# MP_RS485.net
KiCad netlist of a schematic drawn in Altium Designer
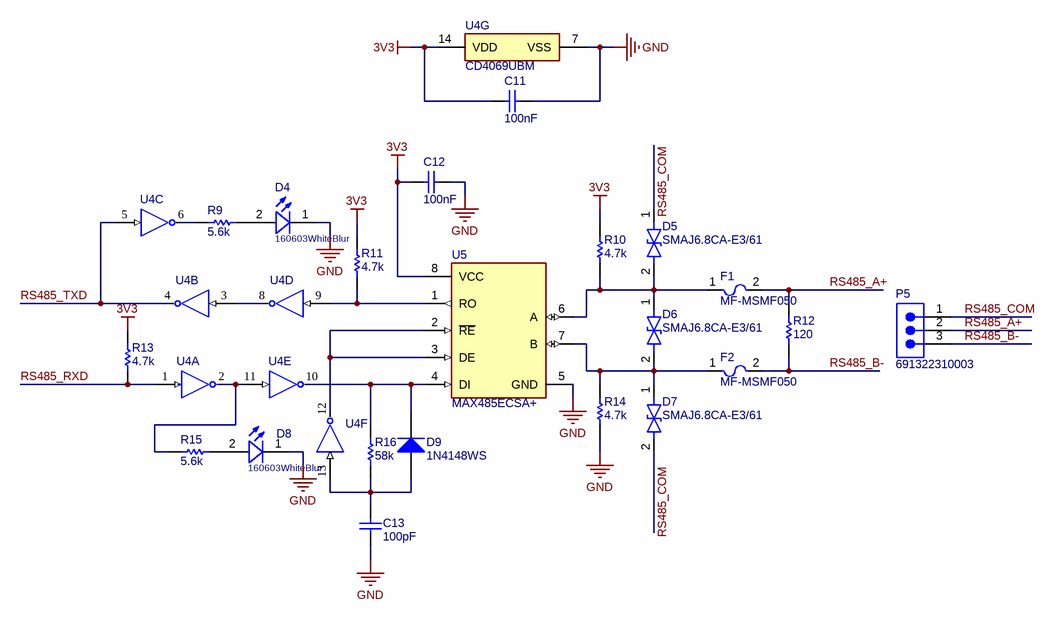
[diagram p0: [MP] RS485.SchDoc]

(export (version "E")
  (design (tool "Eeschema 10.0.6"))
  (components
    (comp (ref "C11")
      (value "100nF")
      (footprint "CAP_0603")
      (description "CAP, size 0603, 100 nF, 50 VDC, 10%")
      (fields
        (field (name "MANUFACTURER PART NUMBER") "CGA3E3X8R1H104K080AE")
        (field (name "LCSC PART #") "C14663")
        (field (name "SOURCE") "Capacitor_0603_10_percent.SchLib")
      )
      (libsource (lib "University of Technology") (part "010603475106.3"))
    )
    (comp (ref "C12")
      (value "100nF")
      (footprint "CAP_0603")
      (description "CAP, size 0603, 100 nF, 50 VDC, 10%")
      (fields
        (field (name "MANUFACTURER PART NUMBER") "CGA3E3X8R1H104K080AE")
        (field (name "LCSC PART #") "C14663")
        (field (name "SOURCE") "Capacitor_0603_10_percent.SchLib")
      )
      (libsource (lib "University of Technology") (part "010603475106.3"))
    )
    (comp (ref "C13")
      (value "100pF")
      (footprint "CAP_0603")
      (description "CAP, size 0603, 100 pF, 50 VDC, 5%")
      (fields
        (field (name "MANUFACTURER") "TDK")
        (field (name "TOLERANCE") "5%")
        (field (name "SOURCE") "Capacitor_0603_5_percent.SchLib")
      )
      (libsource (lib "University of Technology") (part "0106036820550"))
    )
    (comp (ref "D4")
      (value "160603WhiteBlur")
      (footprint "WL-SMCW_0603_H=0.7mm")
      (description "WL-SMCW SMT Mono-color Chip LED Blur, size 0603, White")
      (libsource (lib "University of Technology") (part "160603WhiteClear"))
    )
    (comp (ref "D5")
      (value "SMAJ6.8CA-E3/61")
      (footprint "VISH-DO-214AC-2_M")
      (description "Trans Voltage Suppressor Diode, 400W, 6V V(RWM), Bidirectional, 1 Element, Silicon, DO-214AC")
      (libsource (lib "University of Technology") (part "SMAJ6.8CA"))
    )
    (comp (ref "D6")
      (value "SMAJ6.8CA-E3/61")
      (footprint "VISH-DO-214AC-2_M")
      (description "Trans Voltage Suppressor Diode, 400W, 6V V(RWM), Bidirectional, 1 Element, Silicon, DO-214AC")
      (libsource (lib "University of Technology") (part "SMAJ6.8CA"))
    )
    (comp (ref "D7")
      (value "SMAJ6.8CA-E3/61")
      (footprint "VISH-DO-214AC-2_M")
      (description "Trans Voltage Suppressor Diode, 400W, 6V V(RWM), Bidirectional, 1 Element, Silicon, DO-214AC")
      (libsource (lib "University of Technology") (part "SMAJ6.8CA"))
    )
    (comp (ref "D8")
      (value "160603WhiteBlur")
      (footprint "WL-SMCW_0603_H=0.7mm")
      (description "WL-SMCW SMT Mono-color Chip LED Blur, size 0603, White")
      (libsource (lib "University of Technology") (part "160603WhiteClear"))
    )
    (comp (ref "D9")
      (value "1N4148WS")
      (footprint "FAIR-SOD-323_V")
      (description "Small Signal Diode, 75 V, 0.15 A, -55 to 150 degC, 2-Pin SOD-323, RoHS, Tape and Reel")
      (fields (field (name "MANUFACTURER") "Fairchild"))
      (libsource (lib "University of Technology") (part "D-AK-2"))
    )
    (comp (ref "F1")
      (value "MF-MSMF050")
      (footprint "BOUR-MF-MSMF050-2_V")
      (description "PTC Resettable Fuse, 15 V, 500 mA, -40 to 85 degC, 2-Pin SMD, RoHS, Tape and Reel")
      (fields (field (name "MANUFACTURER") "Bourns"))
      (libsource (lib "University of Technology") (part "FUSE-2"))
    )
    (comp (ref "F2")
      (value "MF-MSMF050")
      (footprint "BOUR-MF-MSMF050-2_V")
      (description "PTC Resettable Fuse, 15 V, 500 mA, -40 to 85 degC, 2-Pin SMD, RoHS, Tape and Reel")
      (fields (field (name "MANUFACTURER") "Bourns"))
      (libsource (lib "University of Technology") (part "FUSE-2"))
    )
    (comp (ref "P5")
      (value "691322310003")
      (footprint "691322310003")
      (description "WR-TBL Series 322 Horizontal PCB Header, THT, pitch 3.81mm, 3p")
      (fields
        (field (name "MANUFACTURER") "Wurth Elektronik")
        (field (name "SOURCE") "Terminal_Blocks_Pluggable_3.81mm.SchLib")
      )
      (libsource (lib "University of Technology") (part "691322310003"))
    )
    (comp (ref "R9")
      (value "5.6k")
      (footprint "RES_0603")
      (description "RES, size 0603, 5.6 KOhm, 1/10 W, 1%")
      (fields (field (name "TOLERANCE") "1%") (field (name "MANUFACTURER PART NUMBER") "OEM"))
      (libsource (lib "University of Technology") (part "00060371541"))
    )
    (comp (ref "R10")
      (value "4.7k")
      (footprint "RES_0603")
      (description "RES, size 0603, 4.7 kOhm, 1/10 W, 1%")
      (fields
        (field (name "LCSC PART #") "C99782")
        (field (name "MANUFACTURER PART NUMBER") "RC0603FR-074K7L")
      )
      (libsource (lib "University of Technology") (part "00060371541"))
    )
    (comp (ref "R11")
      (value "4.7k")
      (footprint "RES_0603")
      (description "RES, size 0603, 4.7 kOhm, 1/10 W, 1%")
      (fields
        (field (name "LCSC PART #") "C99782")
        (field (name "MANUFACTURER PART NUMBER") "RC0603FR-074K7L")
      )
      (libsource (lib "University of Technology") (part "00060371541"))
    )
    (comp (ref "R12")
      (value "120")
      (footprint "RES_0603")
      (description "RES, size 0603, 120 Ohm, 1/10 W, 5%")
      (fields (field (name "MANUFACTURER PART NUMBER") "ERJ-PA3J121V") (field (name "TOLERANCE") "5%"))
      (libsource (lib "University of Technology") (part "00060371541"))
    )
    (comp (ref "R13")
      (value "4.7k")
      (footprint "RES_0603")
      (description "RES, size 0603, 4.7 kOhm, 1/10 W, 1%")
      (fields
        (field (name "LCSC PART #") "C99782")
        (field (name "MANUFACTURER PART NUMBER") "RC0603FR-074K7L")
      )
      (libsource (lib "University of Technology") (part "00060371541"))
    )
    (comp (ref "R14")
      (value "4.7k")
      (footprint "RES_0603")
      (description "RES, size 0603, 4.7 kOhm, 1/10 W, 1%")
      (fields
        (field (name "LCSC PART #") "C99782")
        (field (name "MANUFACTURER PART NUMBER") "RC0603FR-074K7L")
      )
      (libsource (lib "University of Technology") (part "00060371541"))
    )
    (comp (ref "R15")
      (value "5.6k")
      (footprint "RES_0603")
      (description "RES, size 0603, 5.6 KOhm, 1/10 W, 1%")
      (fields (field (name "TOLERANCE") "1%") (field (name "MANUFACTURER PART NUMBER") "OEM"))
      (libsource (lib "University of Technology") (part "00060371541"))
    )
    (comp (ref "R16")
      (value "58k")
      (footprint "RES_0603")
      (description "RES, size 0603, 58 KOhm, 1/10 W, 5%")
      (fields (field (name "MANUFACTURER") "OEM") (field (name "TOLERANCE") "5%"))
      (libsource (lib "University of Technology") (part "00060371541"))
    )
    (comp (ref "U4")
      (value "CD4069UBM")
      (footprint "FP-D0014A-MFG")
      (description "Inverter, 4000/14000/40000 Series, 6-Func, 1-Input, CMOS, PDSO14")
      (libsource (lib "University of Technology") (part "6cab11a98d2aa11df0b3da3ab29e1f3"))
    )
    (comp (ref "U5")
      (value "MAX485ECSA+")
      (footprint "FP-S8-5-MFG")
      (description "Line Transceiver, 1 Func, 1 Driver, 1 Rcvr, CMOS, PDSO8")
      (libsource (lib "University of Technology") (part "a5e355d41674bc2bebc6d79e25ee122"))
    )
  )
  (nets
    (net (code "1") (name "/RS485_A+") (class "Default")
      (node (ref "F1") (pin "2") (pinfunction "2_2") (pintype "passive"))
      (node (ref "P5") (pin "2") (pinfunction "2_2") (pintype "passive"))
      (node (ref "R12") (pin "2") (pinfunction "2_2") (pintype "passive"))
    )
    (net (code "2") (name "/RS485_B-") (class "Default")
      (node (ref "F2") (pin "2") (pinfunction "2_2") (pintype "passive"))
      (node (ref "P5") (pin "3") (pinfunction "3_3") (pintype "passive"))
      (node (ref "R12") (pin "1") (pinfunction "1_1") (pintype "passive"))
    )
    (net (code "3") (name "/RS485_COM") (class "Default")
      (node (ref "D5") (pin "1") (pinfunction "K_1") (pintype "passive"))
      (node (ref "D7") (pin "2") (pinfunction "A_2") (pintype "passive"))
      (node (ref "P5") (pin "1") (pinfunction "1_1") (pintype "passive"))
    )
    (net (code "4") (name "/RS485_RXD") (class "Default")
      (node (ref "R13") (pin "2") (pinfunction "2_2") (pintype "passive"))
      (node (ref "U4") (pin "1") (pinfunction "A_1") (pintype "input"))
    )
    (net (code "5") (name "/RS485_TXD") (class "Default")
      (node (ref "U4") (pin "4") (pinfunction "~{B}_4") (pintype "output"))
      (node (ref "U4") (pin "5") (pinfunction "C_5") (pintype "input"))
    )
    (net (code "6") (name "3V3") (class "Default")
      (node (ref "C11") (pin "2") (pinfunction "2_2") (pintype "passive"))
      (node (ref "C12") (pin "2") (pinfunction "2_2") (pintype "passive"))
      (node (ref "R10") (pin "1") (pinfunction "1_1") (pintype "passive"))
      (node (ref "R11") (pin "1") (pinfunction "1_1") (pintype "passive"))
      (node (ref "R13") (pin "1") (pinfunction "1_1") (pintype "passive"))
      (node (ref "U4") (pin "14") (pinfunction "VDD_14") (pintype "power_in"))
      (node (ref "U5") (pin "8") (pinfunction "VCC_8") (pintype "power_in"))
    )
    (net (code "7") (name "GND") (class "Default")
      (node (ref "C11") (pin "1") (pinfunction "1_1") (pintype "passive"))
      (node (ref "C12") (pin "1") (pinfunction "1_1") (pintype "passive"))
      (node (ref "C13") (pin "1") (pinfunction "1_1") (pintype "passive"))
      (node (ref "D4") (pin "1") (pinfunction "K_1") (pintype "passive"))
      (node (ref "D8") (pin "1") (pinfunction "K_1") (pintype "passive"))
      (node (ref "R14") (pin "2") (pinfunction "2_2") (pintype "passive"))
      (node (ref "U4") (pin "7") (pinfunction "VSS_7") (pintype "power_in"))
      (node (ref "U5") (pin "5") (pinfunction "GND_5") (pintype "power_in"))
    )
    (net (code "8") (name "Net-(D4-A)") (class "Default")
      (node (ref "D4") (pin "2") (pinfunction "A_2") (pintype "passive"))
      (node (ref "R9") (pin "2") (pinfunction "2_2") (pintype "passive"))
    )
    (net (code "9") (name "Net-(D5-A)") (class "Default")
      (node (ref "D5") (pin "2") (pinfunction "A_2") (pintype "passive"))
      (node (ref "D6") (pin "1") (pinfunction "K_1") (pintype "passive"))
      (node (ref "F1") (pin "1") (pinfunction "1_1") (pintype "passive"))
      (node (ref "R10") (pin "2") (pinfunction "2_2") (pintype "passive"))
      (node (ref "U5") (pin "6") (pinfunction "A_6") (pintype "bidirectional"))
    )
    (net (code "10") (name "Net-(D6-A)") (class "Default")
      (node (ref "D6") (pin "2") (pinfunction "A_2") (pintype "passive"))
      (node (ref "D7") (pin "1") (pinfunction "K_1") (pintype "passive"))
      (node (ref "F2") (pin "1") (pinfunction "1_1") (pintype "passive"))
      (node (ref "R14") (pin "1") (pinfunction "1_1") (pintype "passive"))
      (node (ref "U5") (pin "7") (pinfunction "B_7") (pintype "bidirectional"))
    )
    (net (code "11") (name "Net-(D8-A)") (class "Default")
      (node (ref "D8") (pin "2") (pinfunction "A_2") (pintype "passive"))
      (node (ref "R15") (pin "2") (pinfunction "2_2") (pintype "passive"))
    )
    (net (code "12") (name "Net-(D9-A)") (class "Default")
      (node (ref "C13") (pin "2") (pinfunction "2_2") (pintype "passive"))
      (node (ref "D9") (pin "1") (pinfunction "A_1") (pintype "passive"))
      (node (ref "R16") (pin "1") (pinfunction "1_1") (pintype "passive"))
      (node (ref "U4") (pin "13") (pinfunction "F_13") (pintype "input"))
    )
    (net (code "13") (name "Net-(D9-K)") (class "Default")
      (node (ref "D9") (pin "2") (pinfunction "K_2") (pintype "passive"))
      (node (ref "R16") (pin "2") (pinfunction "2_2") (pintype "passive"))
      (node (ref "U4") (pin "10") (pinfunction "~{E}_10") (pintype "output"))
      (node (ref "U5") (pin "4") (pinfunction "DI_4") (pintype "input"))
    )
    (net (code "14") (name "Net-(U4A-~{A})") (class "Default")
      (node (ref "R15") (pin "1") (pinfunction "1_1") (pintype "passive"))
      (node (ref "U4") (pin "11") (pinfunction "E_11") (pintype "input"))
      (node (ref "U4") (pin "2") (pinfunction "~{A}_2") (pintype "output"))
    )
    (net (code "15") (name "Net-(U4B-B)") (class "Default")
      (node (ref "U4") (pin "3") (pinfunction "B_3") (pintype "input"))
      (node (ref "U4") (pin "8") (pinfunction "~{D}_8") (pintype "output"))
    )
    (net (code "16") (name "Net-(U4C-~{C})") (class "Default")
      (node (ref "R9") (pin "1") (pinfunction "1_1") (pintype "passive"))
      (node (ref "U4") (pin "6") (pinfunction "~{C}_6") (pintype "output"))
    )
    (net (code "17") (name "Net-(U4D-D)") (class "Default")
      (node (ref "R11") (pin "2") (pinfunction "2_2") (pintype "passive"))
      (node (ref "U4") (pin "9") (pinfunction "D_9") (pintype "input"))
      (node (ref "U5") (pin "1") (pinfunction "RO_1") (pintype "output"))
    )
    (net (code "18") (name "Net-(U4F-~{F})") (class "Default")
      (node (ref "U4") (pin "12") (pinfunction "~{F}_12") (pintype "output"))
      (node (ref "U5") (pin "2") (pinfunction "~{RE}_2") (pintype "input"))
      (node (ref "U5") (pin "3") (pinfunction "DE_3") (pintype "input"))
    )
  )
)
